# Nusbio_smd.net
KiCad netlist of a schematic drawn in EAGLE
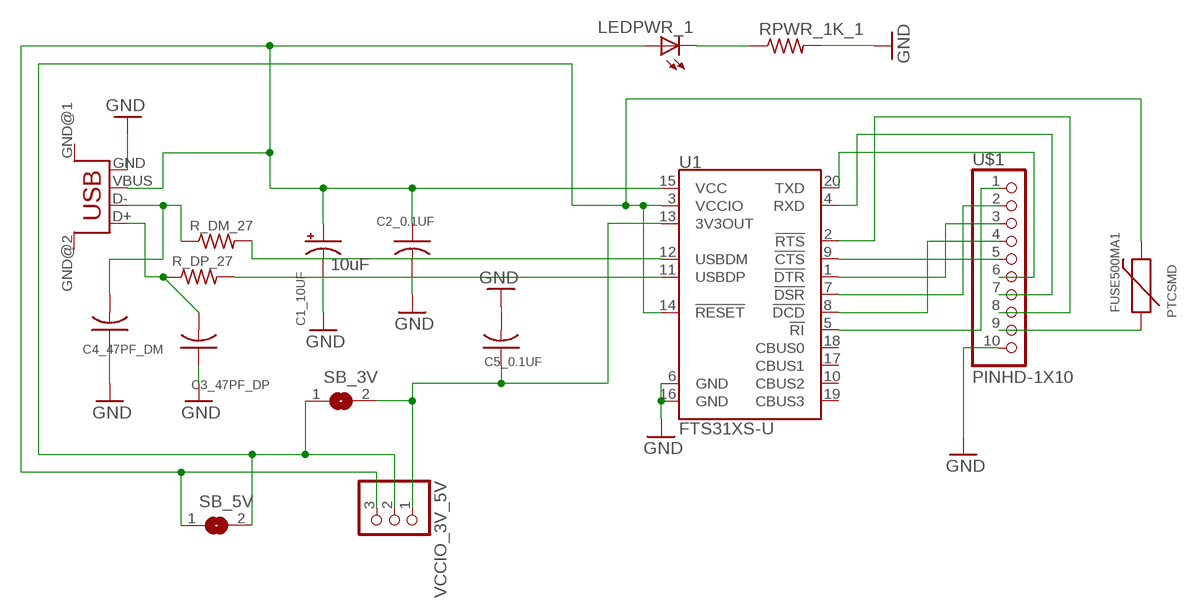
[diagram p0: schematic, sheet 1]

(export (version "E")
  (design (tool "Eeschema 10.0.6"))
  (components
    (comp (ref "C1_10UF")
      (value "10uF")
      (footprint "eagle-import:EIA3216")
      (libsource (lib "eagle-import") (part "10UF-16V-10%(TANT)"))
    )
    (comp (ref "C2_0.1UF")
      (value "C-USC1206")
      (footprint "eagle-import:C1206")
      (libsource (lib "eagle-import") (part "C-USC1206"))
    )
    (comp (ref "C3_47PF_DP")
      (value "C-USC1206")
      (footprint "eagle-import:C1206")
      (libsource (lib "eagle-import") (part "C-USC1206"))
    )
    (comp (ref "C4_47PF_DM")
      (value "C-USC1206")
      (footprint "eagle-import:C1206")
      (libsource (lib "eagle-import") (part "C-USC1206"))
    )
    (comp (ref "C5_0.1UF")
      (value "C-USC1206")
      (footprint "eagle-import:C1206")
      (libsource (lib "eagle-import") (part "C-USC1206"))
    )
    (comp (ref "FUSE500MA1")
      (value "PTCSMD")
      (footprint "eagle-import:PTC-1206")
      (libsource (lib "eagle-import") (part "PTCSMD"))
    )
    (comp (ref "LEDPWR_1")
      (value "LEDCHIPLED_0805")
      (footprint "eagle-import:CHIPLED_0805")
      (libsource (lib "eagle-import") (part "LEDCHIPLED_0805"))
    )
    (comp (ref "RPWR_1K_1")
      (value "R-US_R0805")
      (footprint "eagle-import:R0805")
      (libsource (lib "eagle-import") (part "R-US_R0805"))
    )
    (comp (ref "R_DM_27")
      (value "R-US_R0805")
      (footprint "eagle-import:R0805")
      (libsource (lib "eagle-import") (part "R-US_R0805"))
    )
    (comp (ref "R_DP_27")
      (value "R-US_R0805")
      (footprint "eagle-import:R0805")
      (libsource (lib "eagle-import") (part "R-US_R0805"))
    )
    (comp (ref "SB_3V")
      (value "SOLDERJUMPERREFLOW")
      (footprint "eagle-import:SOLDERJUMPER_REFLOW")
      (libsource (lib "eagle-import") (part "SOLDERJUMPERREFLOW"))
    )
    (comp (ref "SB_5V")
      (value "SOLDERJUMPERREFLOW")
      (footprint "eagle-import:SOLDERJUMPER_REFLOW")
      (libsource (lib "eagle-import") (part "SOLDERJUMPERREFLOW"))
    )
    (comp (ref "U$1")
      (value "PINHD-1X10")
      (footprint "eagle-import:1X10-BIG")
      (libsource (lib "eagle-import") (part "PINHD-1X10"))
    )
    (comp (ref "U1")
      (value "FTS31XS-U")
      (footprint "eagle-import:SSOP20_L")
      (libsource (lib "eagle-import") (part "FT231XS"))
    )
    (comp (ref "USB_FEMALE")
      (value "USB")
      (footprint "eagle-import:USB-FEMALE-A-PTH")
      (libsource (lib "eagle-import") (part "USB"))
    )
    (comp (ref "VCCIO_3V_5V")
      (value "PINHD-1X3")
      (footprint "eagle-import:1X03")
      (libsource (lib "eagle-import") (part "PINHD-1X3"))
    )
  )
  (nets
    (net (code "1") (name "GND") (class "Default")
      (node (ref "C1_10UF") (pin "C") (pinfunction "-_C") (pintype "passive"))
      (node (ref "C2_0.1UF") (pin "2") (pinfunction "2_2") (pintype "passive"))
      (node (ref "C3_47PF_DP") (pin "1") (pinfunction "1_1") (pintype "passive"))
      (node (ref "C4_47PF_DM") (pin "1") (pinfunction "1_1") (pintype "passive"))
      (node (ref "C5_0.1UF") (pin "2") (pinfunction "2_2") (pintype "passive"))
      (node (ref "RPWR_1K_1") (pin "2") (pinfunction "2_2") (pintype "passive"))
      (node (ref "U$1") (pin "10") (pinfunction "10_10") (pintype "passive"))
      (node (ref "U1") (pin "16") (pinfunction "GND_16") (pintype "bidirectional"))
      (node (ref "U1") (pin "6") (pinfunction "GND_6") (pintype "bidirectional"))
      (node (ref "USB_FEMALE") (pin "GND") (pinfunction "GND_GND") (pintype "bidirectional"))
    )
    (net (code "2") (name "Net-(C1_10UF-+)") (class "Default")
      (node (ref "C1_10UF") (pin "A") (pinfunction "+_A") (pintype "passive"))
      (node (ref "C2_0.1UF") (pin "1") (pinfunction "1_1") (pintype "passive"))
      (node (ref "LEDPWR_1") (pin "A") (pinfunction "A_A") (pintype "passive"))
      (node (ref "SB_5V") (pin "1") (pinfunction "1_1") (pintype "passive"))
      (node (ref "U1") (pin "15") (pinfunction "VCC_15") (pintype "bidirectional"))
      (node (ref "USB_FEMALE") (pin "VBUS") (pinfunction "VBUS_VBUS") (pintype "bidirectional"))
      (node (ref "VCCIO_3V_5V") (pin "3") (pinfunction "3_3") (pintype "passive"))
    )
    (net (code "3") (name "Net-(C3_47PF_DP-Pad2)") (class "Default")
      (node (ref "C3_47PF_DP") (pin "2") (pinfunction "2_2") (pintype "passive"))
      (node (ref "R_DP_27") (pin "1") (pinfunction "1_1") (pintype "passive"))
      (node (ref "USB_FEMALE") (pin "D+") (pinfunction "D+_D+") (pintype "bidirectional"))
    )
    (net (code "4") (name "Net-(C4_47PF_DM-Pad2)") (class "Default")
      (node (ref "C4_47PF_DM") (pin "2") (pinfunction "2_2") (pintype "passive"))
      (node (ref "R_DM_27") (pin "1") (pinfunction "1_1") (pintype "passive"))
      (node (ref "USB_FEMALE") (pin "D-") (pinfunction "D-_D-") (pintype "bidirectional"))
    )
    (net (code "5") (name "Net-(FUSE500MA1-Pad1)") (class "Default")
      (node (ref "FUSE500MA1") (pin "1") (pinfunction "1_1") (pintype "bidirectional"))
      (node (ref "U$1") (pin "9") (pinfunction "9_9") (pintype "passive"))
    )
    (net (code "6") (name "Net-(LEDPWR_1-PadC)") (class "Default")
      (node (ref "LEDPWR_1") (pin "C") (pinfunction "C_C") (pintype "passive"))
      (node (ref "RPWR_1K_1") (pin "1") (pinfunction "1_1") (pintype "passive"))
    )
    (net (code "7") (name "Net-(U1-3V3OUT)") (class "Default")
      (node (ref "C5_0.1UF") (pin "1") (pinfunction "1_1") (pintype "passive"))
      (node (ref "SB_3V") (pin "2") (pinfunction "2_2") (pintype "passive"))
      (node (ref "U1") (pin "13") (pinfunction "3V3OUT_13") (pintype "bidirectional"))
      (node (ref "VCCIO_3V_5V") (pin "1") (pinfunction "1_1") (pintype "passive"))
    )
    (net (code "8") (name "Net-(U1-RXD)") (class "Default")
      (node (ref "U$1") (pin "7") (pinfunction "7_7") (pintype "passive"))
      (node (ref "U1") (pin "4") (pinfunction "RXD_4") (pintype "bidirectional"))
    )
    (net (code "9") (name "Net-(U1-TXD)") (class "Default")
      (node (ref "U$1") (pin "6") (pinfunction "6_6") (pintype "passive"))
      (node (ref "U1") (pin "20") (pinfunction "TXD_20") (pintype "bidirectional"))
    )
    (net (code "10") (name "Net-(U1-USBDM)") (class "Default")
      (node (ref "R_DM_27") (pin "2") (pinfunction "2_2") (pintype "passive"))
      (node (ref "U1") (pin "12") (pinfunction "USBDM_12") (pintype "bidirectional"))
    )
    (net (code "11") (name "Net-(U1-USBDP)") (class "Default")
      (node (ref "R_DP_27") (pin "2") (pinfunction "2_2") (pintype "passive"))
      (node (ref "U1") (pin "11") (pinfunction "USBDP_11") (pintype "bidirectional"))
    )
    (net (code "12") (name "Net-(U1-VCCIO)") (class "Default")
      (node (ref "FUSE500MA1") (pin "2") (pinfunction "2_2") (pintype "bidirectional"))
      (node (ref "SB_3V") (pin "1") (pinfunction "1_1") (pintype "passive"))
      (node (ref "SB_5V") (pin "2") (pinfunction "2_2") (pintype "passive"))
      (node (ref "U1") (pin "14") (pinfunction "~{RESET}_14") (pintype "bidirectional"))
      (node (ref "U1") (pin "3") (pinfunction "VCCIO_3") (pintype "bidirectional"))
      (node (ref "VCCIO_3V_5V") (pin "2") (pinfunction "2_2") (pintype "passive"))
    )
    (net (code "13") (name "Net-(U1-~{CTS})") (class "Default")
      (node (ref "U$1") (pin "5") (pinfunction "5_5") (pintype "passive"))
      (node (ref "U1") (pin "9") (pinfunction "~{CTS}_9") (pintype "bidirectional"))
    )
    (net (code "14") (name "Net-(U1-~{DCD})") (class "Default")
      (node (ref "U$1") (pin "4") (pinfunction "4_4") (pintype "passive"))
      (node (ref "U1") (pin "8") (pinfunction "~{DCD}_8") (pintype "bidirectional"))
    )
    (net (code "15") (name "Net-(U1-~{DSR})") (class "Default")
      (node (ref "U$1") (pin "2") (pinfunction "2_2") (pintype "passive"))
      (node (ref "U1") (pin "7") (pinfunction "~{DSR}_7") (pintype "bidirectional"))
    )
    (net (code "16") (name "Net-(U1-~{DTR})") (class "Default")
      (node (ref "U$1") (pin "3") (pinfunction "3_3") (pintype "passive"))
      (node (ref "U1") (pin "1") (pinfunction "~{DTR}_1") (pintype "bidirectional"))
    )
    (net (code "17") (name "Net-(U1-~{RI})") (class "Default")
      (node (ref "U$1") (pin "1") (pinfunction "1_1") (pintype "passive"))
      (node (ref "U1") (pin "5") (pinfunction "~{RI}_5") (pintype "bidirectional"))
    )
    (net (code "18") (name "Net-(U1-~{RTS})") (class "Default")
      (node (ref "U$1") (pin "8") (pinfunction "8_8") (pintype "passive"))
      (node (ref "U1") (pin "2") (pinfunction "~{RTS}_2") (pintype "bidirectional"))
    )
    (net (code "19") (name "unconnected-(U1-CBUS0-Pad18)") (class "Default")
      (node (ref "U1") (pin "18") (pinfunction "CBUS0_18") (pintype "bidirectional"))
    )
    (net (code "20") (name "unconnected-(U1-CBUS1-Pad17)") (class "Default")
      (node (ref "U1") (pin "17") (pinfunction "CBUS1_17") (pintype "bidirectional"))
    )
    (net (code "21") (name "unconnected-(U1-CBUS2-Pad10)") (class "Default")
      (node (ref "U1") (pin "10") (pinfunction "CBUS2_10") (pintype "bidirectional"))
    )
    (net (code "22") (name "unconnected-(U1-CBUS3-Pad19)") (class "Default")
      (node (ref "U1") (pin "19") (pinfunction "CBUS3_19") (pintype "bidirectional"))
    )
    (net (code "23") (name "unconnected-(USB_FEMALE-GND-PadGND@1)") (class "Default")
      (node (ref "USB_FEMALE") (pin "GND@1") (pinfunction "GND_GND@1") (pintype "bidirectional"))
    )
    (net (code "24") (name "unconnected-(USB_FEMALE-GND-PadGND@2)") (class "Default")
      (node (ref "USB_FEMALE") (pin "GND@2") (pinfunction "GND_GND@2") (pintype "bidirectional"))
    )
  )
)
